# LED_Matrix.net
KiCad netlist of a schematic drawn in Altium Designer
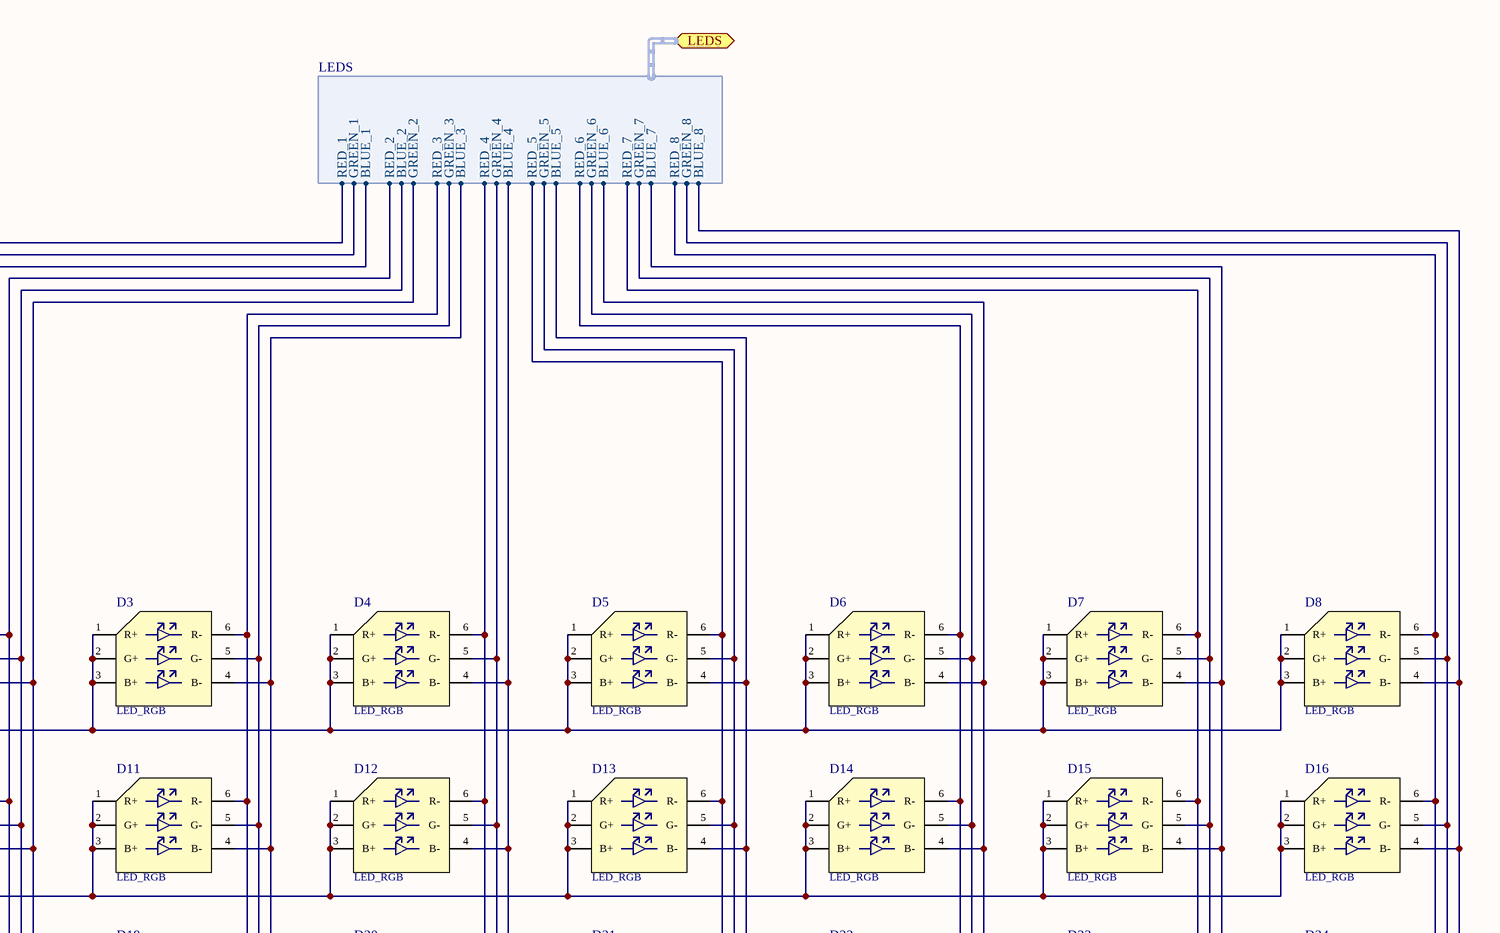
[diagram p0: LED Matrix.SchDoc, top right]
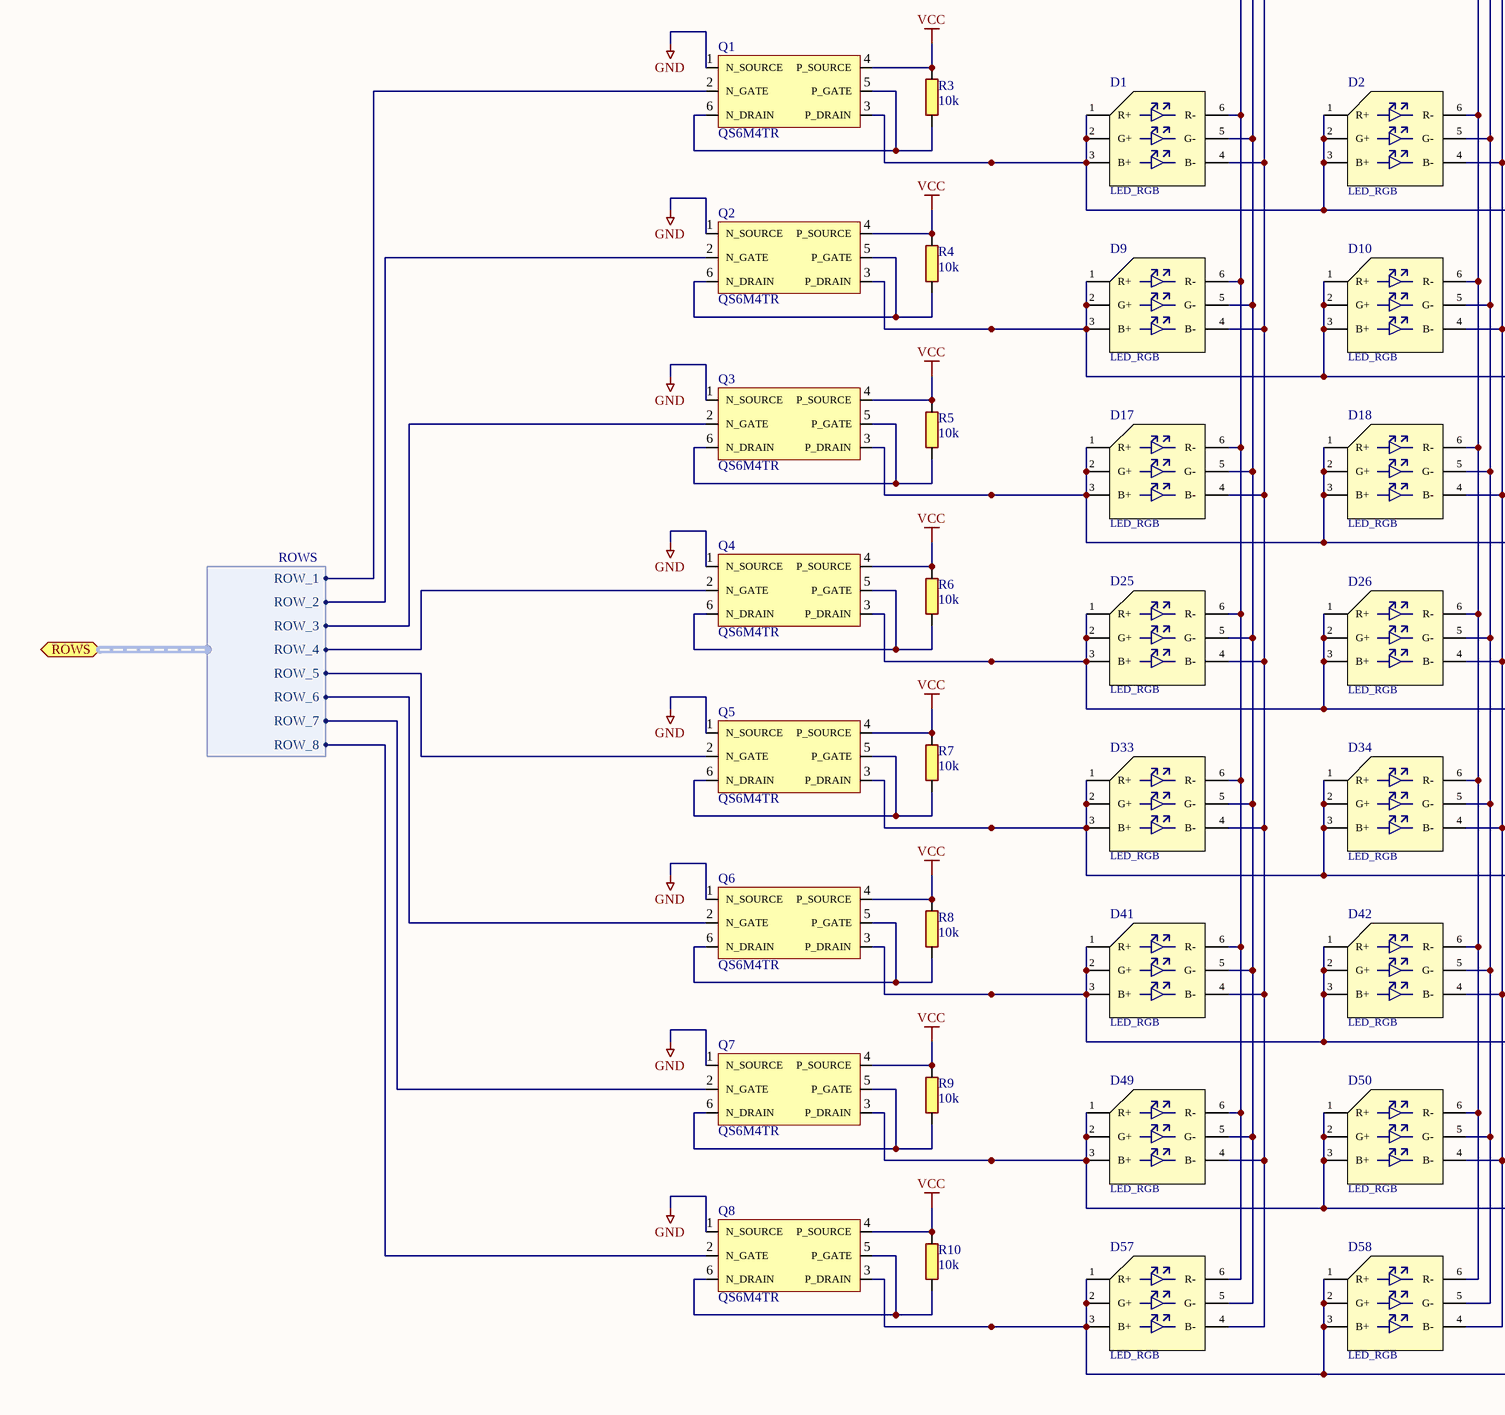
[diagram p1: LED Matrix.SchDoc, bottom left]
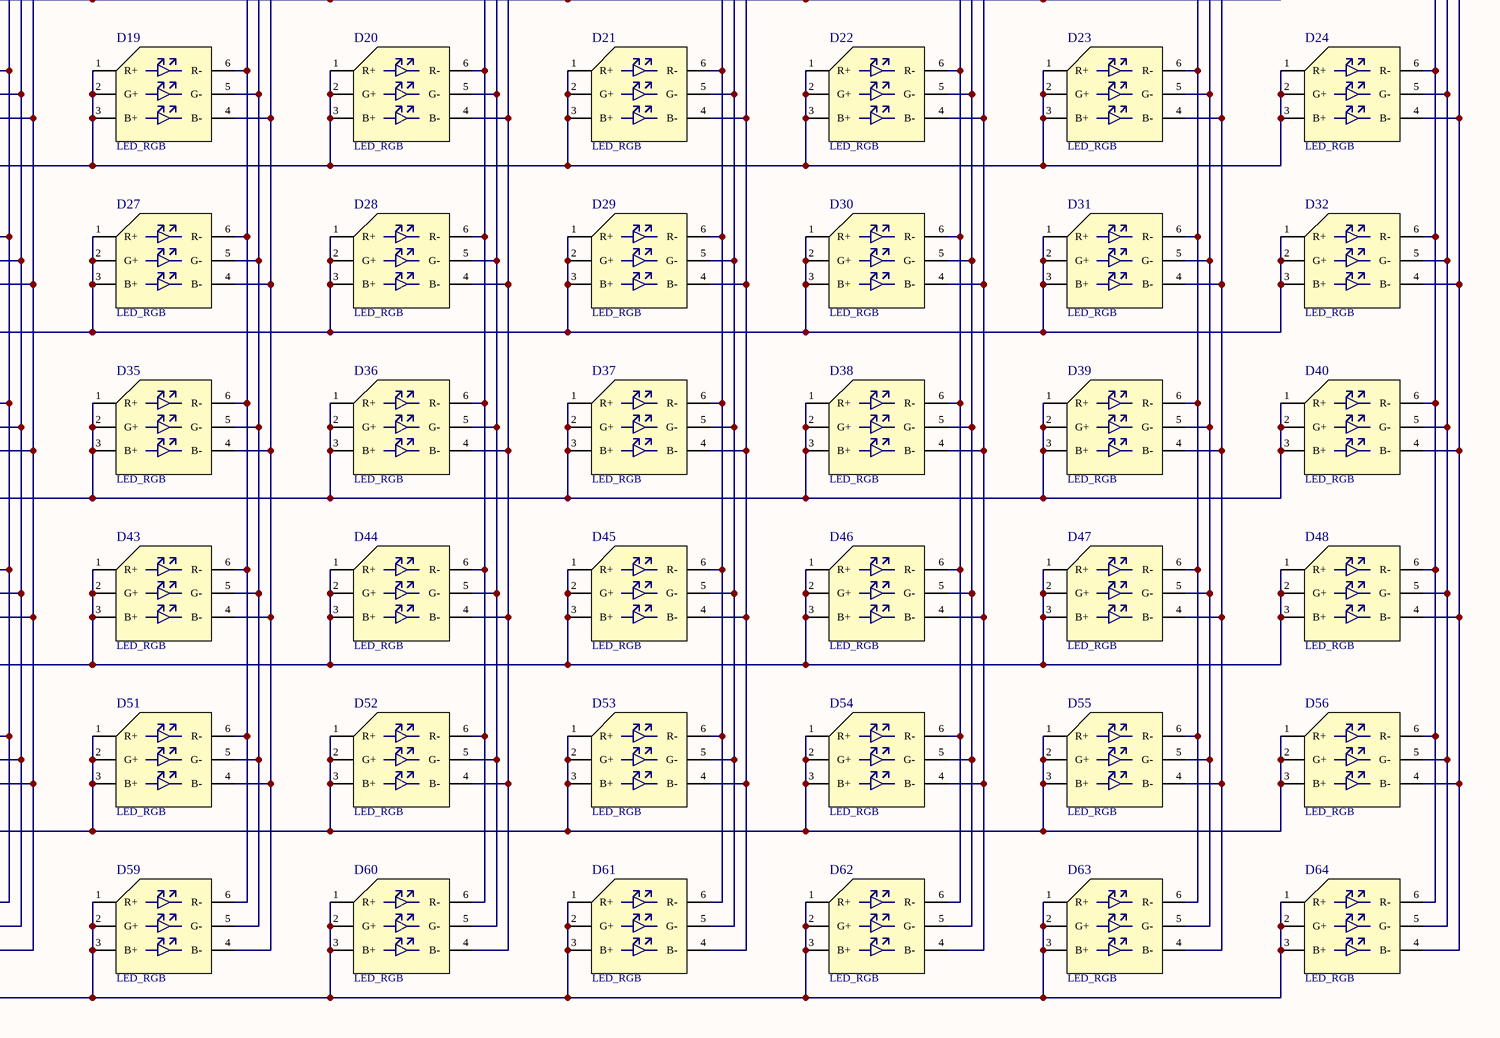
[diagram p2: LED Matrix.SchDoc, bottom right]

(export (version "E")
  (design (tool "Eeschema 10.0.6"))
  (components
    (comp (ref "D1")
      (value "LED_RGB")
      (footprint "LED5050_RGB_N")
      (description "LED RGB, independent colors")
      (libsource (lib "OVLib") (part "LED_RGB_IND_CHIP"))
    )
    (comp (ref "D2")
      (value "LED_RGB")
      (footprint "LED5050_RGB_N")
      (description "LED RGB, independent colors")
      (libsource (lib "OVLib") (part "LED_RGB_IND_CHIP"))
    )
    (comp (ref "D3")
      (value "LED_RGB")
      (footprint "LED5050_RGB_N")
      (description "LED RGB, independent colors")
      (libsource (lib "OVLib") (part "LED_RGB_IND_CHIP"))
    )
    (comp (ref "D4")
      (value "LED_RGB")
      (footprint "LED5050_RGB_N")
      (description "LED RGB, independent colors")
      (libsource (lib "OVLib") (part "LED_RGB_IND_CHIP"))
    )
    (comp (ref "D5")
      (value "LED_RGB")
      (footprint "LED5050_RGB_N")
      (description "LED RGB, independent colors")
      (libsource (lib "OVLib") (part "LED_RGB_IND_CHIP"))
    )
    (comp (ref "D6")
      (value "LED_RGB")
      (footprint "LED5050_RGB_N")
      (description "LED RGB, independent colors")
      (libsource (lib "OVLib") (part "LED_RGB_IND_CHIP"))
    )
    (comp (ref "D7")
      (value "LED_RGB")
      (footprint "LED5050_RGB_N")
      (description "LED RGB, independent colors")
      (libsource (lib "OVLib") (part "LED_RGB_IND_CHIP"))
    )
    (comp (ref "D8")
      (value "LED_RGB")
      (footprint "LED5050_RGB_N")
      (description "LED RGB, independent colors")
      (libsource (lib "OVLib") (part "LED_RGB_IND_CHIP"))
    )
    (comp (ref "D9")
      (value "LED_RGB")
      (footprint "LED5050_RGB_N")
      (description "LED RGB, independent colors")
      (libsource (lib "OVLib") (part "LED_RGB_IND_CHIP"))
    )
    (comp (ref "D10")
      (value "LED_RGB")
      (footprint "LED5050_RGB_N")
      (description "LED RGB, independent colors")
      (libsource (lib "OVLib") (part "LED_RGB_IND_CHIP"))
    )
    (comp (ref "D11")
      (value "LED_RGB")
      (footprint "LED5050_RGB_N")
      (description "LED RGB, independent colors")
      (libsource (lib "OVLib") (part "LED_RGB_IND_CHIP"))
    )
    (comp (ref "D12")
      (value "LED_RGB")
      (footprint "LED5050_RGB_N")
      (description "LED RGB, independent colors")
      (libsource (lib "OVLib") (part "LED_RGB_IND_CHIP"))
    )
    (comp (ref "D13")
      (value "LED_RGB")
      (footprint "LED5050_RGB_N")
      (description "LED RGB, independent colors")
      (libsource (lib "OVLib") (part "LED_RGB_IND_CHIP"))
    )
    (comp (ref "D14")
      (value "LED_RGB")
      (footprint "LED5050_RGB_N")
      (description "LED RGB, independent colors")
      (libsource (lib "OVLib") (part "LED_RGB_IND_CHIP"))
    )
    (comp (ref "D15")
      (value "LED_RGB")
      (footprint "LED5050_RGB_N")
      (description "LED RGB, independent colors")
      (libsource (lib "OVLib") (part "LED_RGB_IND_CHIP"))
    )
    (comp (ref "D16")
      (value "LED_RGB")
      (footprint "LED5050_RGB_N")
      (description "LED RGB, independent colors")
      (libsource (lib "OVLib") (part "LED_RGB_IND_CHIP"))
    )
    (comp (ref "D17")
      (value "LED_RGB")
      (footprint "LED5050_RGB_N")
      (description "LED RGB, independent colors")
      (libsource (lib "OVLib") (part "LED_RGB_IND_CHIP"))
    )
    (comp (ref "D18")
      (value "LED_RGB")
      (footprint "LED5050_RGB_N")
      (description "LED RGB, independent colors")
      (libsource (lib "OVLib") (part "LED_RGB_IND_CHIP"))
    )
    (comp (ref "D19")
      (value "LED_RGB")
      (footprint "LED5050_RGB_N")
      (description "LED RGB, independent colors")
      (libsource (lib "OVLib") (part "LED_RGB_IND_CHIP"))
    )
    (comp (ref "D20")
      (value "LED_RGB")
      (footprint "LED5050_RGB_N")
      (description "LED RGB, independent colors")
      (libsource (lib "OVLib") (part "LED_RGB_IND_CHIP"))
    )
    (comp (ref "D21")
      (value "LED_RGB")
      (footprint "LED5050_RGB_N")
      (description "LED RGB, independent colors")
      (libsource (lib "OVLib") (part "LED_RGB_IND_CHIP"))
    )
    (comp (ref "D22")
      (value "LED_RGB")
      (footprint "LED5050_RGB_N")
      (description "LED RGB, independent colors")
      (libsource (lib "OVLib") (part "LED_RGB_IND_CHIP"))
    )
    (comp (ref "D23")
      (value "LED_RGB")
      (footprint "LED5050_RGB_N")
      (description "LED RGB, independent colors")
      (libsource (lib "OVLib") (part "LED_RGB_IND_CHIP"))
    )
    (comp (ref "D24")
      (value "LED_RGB")
      (footprint "LED5050_RGB_N")
      (description "LED RGB, independent colors")
      (libsource (lib "OVLib") (part "LED_RGB_IND_CHIP"))
    )
    (comp (ref "D25")
      (value "LED_RGB")
      (footprint "LED5050_RGB_N")
      (description "LED RGB, independent colors")
      (libsource (lib "OVLib") (part "LED_RGB_IND_CHIP"))
    )
    (comp (ref "D26")
      (value "LED_RGB")
      (footprint "LED5050_RGB_N")
      (description "LED RGB, independent colors")
      (libsource (lib "OVLib") (part "LED_RGB_IND_CHIP"))
    )
    (comp (ref "D27")
      (value "LED_RGB")
      (footprint "LED5050_RGB_N")
      (description "LED RGB, independent colors")
      (libsource (lib "OVLib") (part "LED_RGB_IND_CHIP"))
    )
    (comp (ref "D28")
      (value "LED_RGB")
      (footprint "LED5050_RGB_N")
      (description "LED RGB, independent colors")
      (libsource (lib "OVLib") (part "LED_RGB_IND_CHIP"))
    )
    (comp (ref "D29")
      (value "LED_RGB")
      (footprint "LED5050_RGB_N")
      (description "LED RGB, independent colors")
      (libsource (lib "OVLib") (part "LED_RGB_IND_CHIP"))
    )
    (comp (ref "D30")
      (value "LED_RGB")
      (footprint "LED5050_RGB_N")
      (description "LED RGB, independent colors")
      (libsource (lib "OVLib") (part "LED_RGB_IND_CHIP"))
    )
    (comp (ref "D31")
      (value "LED_RGB")
      (footprint "LED5050_RGB_N")
      (description "LED RGB, independent colors")
      (libsource (lib "OVLib") (part "LED_RGB_IND_CHIP"))
    )
    (comp (ref "D32")
      (value "LED_RGB")
      (footprint "LED5050_RGB_N")
      (description "LED RGB, independent colors")
      (libsource (lib "OVLib") (part "LED_RGB_IND_CHIP"))
    )
    (comp (ref "D33")
      (value "LED_RGB")
      (footprint "LED5050_RGB_N")
      (description "LED RGB, independent colors")
      (libsource (lib "OVLib") (part "LED_RGB_IND_CHIP"))
    )
    (comp (ref "D34")
      (value "LED_RGB")
      (footprint "LED5050_RGB_N")
      (description "LED RGB, independent colors")
      (libsource (lib "OVLib") (part "LED_RGB_IND_CHIP"))
    )
    (comp (ref "D35")
      (value "LED_RGB")
      (footprint "LED5050_RGB_N")
      (description "LED RGB, independent colors")
      (libsource (lib "OVLib") (part "LED_RGB_IND_CHIP"))
    )
    (comp (ref "D36")
      (value "LED_RGB")
      (footprint "LED5050_RGB_N")
      (description "LED RGB, independent colors")
      (libsource (lib "OVLib") (part "LED_RGB_IND_CHIP"))
    )
    (comp (ref "D37")
      (value "LED_RGB")
      (footprint "LED5050_RGB_N")
      (description "LED RGB, independent colors")
      (libsource (lib "OVLib") (part "LED_RGB_IND_CHIP"))
    )
    (comp (ref "D38")
      (value "LED_RGB")
      (footprint "LED5050_RGB_N")
      (description "LED RGB, independent colors")
      (libsource (lib "OVLib") (part "LED_RGB_IND_CHIP"))
    )
    (comp (ref "D39")
      (value "LED_RGB")
      (footprint "LED5050_RGB_N")
      (description "LED RGB, independent colors")
      (libsource (lib "OVLib") (part "LED_RGB_IND_CHIP"))
    )
    (comp (ref "D40")
      (value "LED_RGB")
      (footprint "LED5050_RGB_N")
      (description "LED RGB, independent colors")
      (libsource (lib "OVLib") (part "LED_RGB_IND_CHIP"))
    )
    (comp (ref "D41")
      (value "LED_RGB")
      (footprint "LED5050_RGB_N")
      (description "LED RGB, independent colors")
      (libsource (lib "OVLib") (part "LED_RGB_IND_CHIP"))
    )
    (comp (ref "D42")
      (value "LED_RGB")
      (footprint "LED5050_RGB_N")
      (description "LED RGB, independent colors")
      (libsource (lib "OVLib") (part "LED_RGB_IND_CHIP"))
    )
    (comp (ref "D43")
      (value "LED_RGB")
      (footprint "LED5050_RGB_N")
      (description "LED RGB, independent colors")
      (libsource (lib "OVLib") (part "LED_RGB_IND_CHIP"))
    )
    (comp (ref "D44")
      (value "LED_RGB")
      (footprint "LED5050_RGB_N")
      (description "LED RGB, independent colors")
      (libsource (lib "OVLib") (part "LED_RGB_IND_CHIP"))
    )
    (comp (ref "D45")
      (value "LED_RGB")
      (footprint "LED5050_RGB_N")
      (description "LED RGB, independent colors")
      (libsource (lib "OVLib") (part "LED_RGB_IND_CHIP"))
    )
    (comp (ref "D46")
      (value "LED_RGB")
      (footprint "LED5050_RGB_N")
      (description "LED RGB, independent colors")
      (libsource (lib "OVLib") (part "LED_RGB_IND_CHIP"))
    )
    (comp (ref "D47")
      (value "LED_RGB")
      (footprint "LED5050_RGB_N")
      (description "LED RGB, independent colors")
      (libsource (lib "OVLib") (part "LED_RGB_IND_CHIP"))
    )
    (comp (ref "D48")
      (value "LED_RGB")
      (footprint "LED5050_RGB_N")
      (description "LED RGB, independent colors")
      (libsource (lib "OVLib") (part "LED_RGB_IND_CHIP"))
    )
    (comp (ref "D49")
      (value "LED_RGB")
      (footprint "LED5050_RGB_N")
      (description "LED RGB, independent colors")
      (libsource (lib "OVLib") (part "LED_RGB_IND_CHIP"))
    )
    (comp (ref "D50")
      (value "LED_RGB")
      (footprint "LED5050_RGB_N")
      (description "LED RGB, independent colors")
      (libsource (lib "OVLib") (part "LED_RGB_IND_CHIP"))
    )
    (comp (ref "D51")
      (value "LED_RGB")
      (footprint "LED5050_RGB_N")
      (description "LED RGB, independent colors")
      (libsource (lib "OVLib") (part "LED_RGB_IND_CHIP"))
    )
    (comp (ref "D52")
      (value "LED_RGB")
      (footprint "LED5050_RGB_N")
      (description "LED RGB, independent colors")
      (libsource (lib "OVLib") (part "LED_RGB_IND_CHIP"))
    )
    (comp (ref "D53")
      (value "LED_RGB")
      (footprint "LED5050_RGB_N")
      (description "LED RGB, independent colors")
      (libsource (lib "OVLib") (part "LED_RGB_IND_CHIP"))
    )
    (comp (ref "D54")
      (value "LED_RGB")
      (footprint "LED5050_RGB_N")
      (description "LED RGB, independent colors")
      (libsource (lib "OVLib") (part "LED_RGB_IND_CHIP"))
    )
    (comp (ref "D55")
      (value "LED_RGB")
      (footprint "LED5050_RGB_N")
      (description "LED RGB, independent colors")
      (libsource (lib "OVLib") (part "LED_RGB_IND_CHIP"))
    )
    (comp (ref "D56")
      (value "LED_RGB")
      (footprint "LED5050_RGB_N")
      (description "LED RGB, independent colors")
      (libsource (lib "OVLib") (part "LED_RGB_IND_CHIP"))
    )
    (comp (ref "D57")
      (value "LED_RGB")
      (footprint "LED5050_RGB_N")
      (description "LED RGB, independent colors")
      (libsource (lib "OVLib") (part "LED_RGB_IND_CHIP"))
    )
    (comp (ref "D58")
      (value "LED_RGB")
      (footprint "LED5050_RGB_N")
      (description "LED RGB, independent colors")
      (libsource (lib "OVLib") (part "LED_RGB_IND_CHIP"))
    )
    (comp (ref "D59")
      (value "LED_RGB")
      (footprint "LED5050_RGB_N")
      (description "LED RGB, independent colors")
      (libsource (lib "OVLib") (part "LED_RGB_IND_CHIP"))
    )
    (comp (ref "D60")
      (value "LED_RGB")
      (footprint "LED5050_RGB_N")
      (description "LED RGB, independent colors")
      (libsource (lib "OVLib") (part "LED_RGB_IND_CHIP"))
    )
    (comp (ref "D61")
      (value "LED_RGB")
      (footprint "LED5050_RGB_N")
      (description "LED RGB, independent colors")
      (libsource (lib "OVLib") (part "LED_RGB_IND_CHIP"))
    )
    (comp (ref "D62")
      (value "LED_RGB")
      (footprint "LED5050_RGB_N")
      (description "LED RGB, independent colors")
      (libsource (lib "OVLib") (part "LED_RGB_IND_CHIP"))
    )
    (comp (ref "D63")
      (value "LED_RGB")
      (footprint "LED5050_RGB_N")
      (description "LED RGB, independent colors")
      (libsource (lib "OVLib") (part "LED_RGB_IND_CHIP"))
    )
    (comp (ref "D64")
      (value "LED_RGB")
      (footprint "LED5050_RGB_N")
      (description "LED RGB, independent colors")
      (libsource (lib "OVLib") (part "LED_RGB_IND_CHIP"))
    )
    (comp (ref "Q1") (value "QS6M4TR") (libsource (lib "Schlib1") (part "QS6M4TR")))
    (comp (ref "Q2") (value "QS6M4TR") (libsource (lib "Schlib1") (part "QS6M4TR")))
    (comp (ref "Q3") (value "QS6M4TR") (libsource (lib "Schlib1") (part "QS6M4TR")))
    (comp (ref "Q4") (value "QS6M4TR") (libsource (lib "Schlib1") (part "QS6M4TR")))
    (comp (ref "Q5") (value "QS6M4TR") (libsource (lib "Schlib1") (part "QS6M4TR")))
    (comp (ref "Q6") (value "QS6M4TR") (libsource (lib "Schlib1") (part "QS6M4TR")))
    (comp (ref "Q7") (value "QS6M4TR") (libsource (lib "Schlib1") (part "QS6M4TR")))
    (comp (ref "Q8") (value "QS6M4TR") (libsource (lib "Schlib1") (part "QS6M4TR")))
    (comp (ref "R3")
      (value "10k")
      (footprint "RESC0603(1608)_N")
      (description "0.1W 1% Thick film resistor")
      (libsource (lib "OVLib") (part "Resistor2"))
    )
    (comp (ref "R4")
      (value "10k")
      (footprint "RESC0603(1608)_N")
      (description "0.1W 1% Thick film resistor")
      (libsource (lib "OVLib") (part "Resistor2"))
    )
    (comp (ref "R5")
      (value "10k")
      (footprint "RESC0603(1608)_N")
      (description "0.1W 1% Thick film resistor")
      (libsource (lib "OVLib") (part "Resistor2"))
    )
    (comp (ref "R6")
      (value "10k")
      (footprint "RESC0603(1608)_N")
      (description "0.1W 1% Thick film resistor")
      (libsource (lib "OVLib") (part "Resistor2"))
    )
    (comp (ref "R7")
      (value "10k")
      (footprint "RESC0603(1608)_N")
      (description "0.1W 1% Thick film resistor")
      (libsource (lib "OVLib") (part "Resistor2"))
    )
    (comp (ref "R8")
      (value "10k")
      (footprint "RESC0603(1608)_N")
      (description "0.1W 1% Thick film resistor")
      (libsource (lib "OVLib") (part "Resistor2"))
    )
    (comp (ref "R9")
      (value "10k")
      (footprint "RESC0603(1608)_N")
      (description "0.1W 1% Thick film resistor")
      (libsource (lib "OVLib") (part "Resistor2"))
    )
    (comp (ref "R10")
      (value "10k")
      (footprint "RESC0603(1608)_N")
      (description "0.1W 1% Thick film resistor")
      (libsource (lib "OVLib") (part "Resistor2"))
    )
  )
  (nets
    (net (code "3") (name "/BLUE_4") (class "Default")
      (node (ref "D12") (pin "4") (pinfunction "B-_4") (pintype "power_in"))
      (node (ref "D20") (pin "4") (pinfunction "B-_4") (pintype "power_in"))
      (node (ref "D28") (pin "4") (pinfunction "B-_4") (pintype "power_in"))
      (node (ref "D36") (pin "4") (pinfunction "B-_4") (pintype "power_in"))
      (node (ref "D4") (pin "4") (pinfunction "B-_4") (pintype "power_in"))
      (node (ref "D44") (pin "4") (pinfunction "B-_4") (pintype "power_in"))
      (node (ref "D52") (pin "4") (pinfunction "B-_4") (pintype "power_in"))
      (node (ref "D60") (pin "4") (pinfunction "B-_4") (pintype "power_in"))
    )
    (net (code "6") (name "GND") (class "Default")
      (node (ref "Q1") (pin "1") (pinfunction "N_SOURCE_1") (pintype "passive"))
      (node (ref "Q2") (pin "1") (pinfunction "N_SOURCE_1") (pintype "passive"))
      (node (ref "Q3") (pin "1") (pinfunction "N_SOURCE_1") (pintype "passive"))
      (node (ref "Q4") (pin "1") (pinfunction "N_SOURCE_1") (pintype "passive"))
      (node (ref "Q5") (pin "1") (pinfunction "N_SOURCE_1") (pintype "passive"))
      (node (ref "Q6") (pin "1") (pinfunction "N_SOURCE_1") (pintype "passive"))
      (node (ref "Q7") (pin "1") (pinfunction "N_SOURCE_1") (pintype "passive"))
      (node (ref "Q8") (pin "1") (pinfunction "N_SOURCE_1") (pintype "passive"))
    )
    (net (code "7") (name "Net-(D1-B+)") (class "Default")
      (node (ref "D1") (pin "1") (pinfunction "R+_1") (pintype "power_in"))
      (node (ref "D1") (pin "2") (pinfunction "G+_2") (pintype "power_in"))
      (node (ref "D1") (pin "3") (pinfunction "B+_3") (pintype "power_in"))
      (node (ref "D2") (pin "1") (pinfunction "R+_1") (pintype "power_in"))
      (node (ref "D2") (pin "2") (pinfunction "G+_2") (pintype "power_in"))
      (node (ref "D2") (pin "3") (pinfunction "B+_3") (pintype "power_in"))
      (node (ref "D3") (pin "1") (pinfunction "R+_1") (pintype "power_in"))
      (node (ref "D3") (pin "2") (pinfunction "G+_2") (pintype "power_in"))
      (node (ref "D3") (pin "3") (pinfunction "B+_3") (pintype "power_in"))
      (node (ref "D4") (pin "1") (pinfunction "R+_1") (pintype "power_in"))
      (node (ref "D4") (pin "2") (pinfunction "G+_2") (pintype "power_in"))
      (node (ref "D4") (pin "3") (pinfunction "B+_3") (pintype "power_in"))
      (node (ref "D5") (pin "1") (pinfunction "R+_1") (pintype "power_in"))
      (node (ref "D5") (pin "2") (pinfunction "G+_2") (pintype "power_in"))
      (node (ref "D5") (pin "3") (pinfunction "B+_3") (pintype "power_in"))
      (node (ref "D6") (pin "1") (pinfunction "R+_1") (pintype "power_in"))
      (node (ref "D6") (pin "2") (pinfunction "G+_2") (pintype "power_in"))
      (node (ref "D6") (pin "3") (pinfunction "B+_3") (pintype "power_in"))
      (node (ref "D7") (pin "1") (pinfunction "R+_1") (pintype "power_in"))
      (node (ref "D7") (pin "2") (pinfunction "G+_2") (pintype "power_in"))
      (node (ref "D7") (pin "3") (pinfunction "B+_3") (pintype "power_in"))
      (node (ref "D8") (pin "1") (pinfunction "R+_1") (pintype "power_in"))
      (node (ref "D8") (pin "2") (pinfunction "G+_2") (pintype "power_in"))
      (node (ref "D8") (pin "3") (pinfunction "B+_3") (pintype "power_in"))
      (node (ref "Q1") (pin "3") (pinfunction "P_DRAIN_3") (pintype "passive"))
    )
    (net (code "8") (name "Net-(D1-B-)") (class "Default")
      (node (ref "D1") (pin "4") (pinfunction "B-_4") (pintype "power_in"))
      (node (ref "D17") (pin "4") (pinfunction "B-_4") (pintype "power_in"))
      (node (ref "D25") (pin "4") (pinfunction "B-_4") (pintype "power_in"))
      (node (ref "D33") (pin "4") (pinfunction "B-_4") (pintype "power_in"))
      (node (ref "D41") (pin "4") (pinfunction "B-_4") (pintype "power_in"))
      (node (ref "D49") (pin "4") (pinfunction "B-_4") (pintype "power_in"))
      (node (ref "D57") (pin "4") (pinfunction "B-_4") (pintype "power_in"))
      (node (ref "D9") (pin "4") (pinfunction "B-_4") (pintype "power_in"))
    )
    (net (code "9") (name "Net-(D1-G-)") (class "Default")
      (node (ref "D1") (pin "5") (pinfunction "G-_5") (pintype "power_in"))
      (node (ref "D17") (pin "5") (pinfunction "G-_5") (pintype "power_in"))
      (node (ref "D25") (pin "5") (pinfunction "G-_5") (pintype "power_in"))
      (node (ref "D33") (pin "5") (pinfunction "G-_5") (pintype "power_in"))
      (node (ref "D41") (pin "5") (pinfunction "G-_5") (pintype "power_in"))
      (node (ref "D49") (pin "5") (pinfunction "G-_5") (pintype "power_in"))
      (node (ref "D57") (pin "5") (pinfunction "G-_5") (pintype "power_in"))
      (node (ref "D9") (pin "5") (pinfunction "G-_5") (pintype "power_in"))
    )
    (net (code "10") (name "Net-(D1-R-)") (class "Default")
      (node (ref "D1") (pin "6") (pinfunction "R-_6") (pintype "power_in"))
      (node (ref "D17") (pin "6") (pinfunction "R-_6") (pintype "power_in"))
      (node (ref "D25") (pin "6") (pinfunction "R-_6") (pintype "power_in"))
      (node (ref "D33") (pin "6") (pinfunction "R-_6") (pintype "power_in"))
      (node (ref "D41") (pin "6") (pinfunction "R-_6") (pintype "power_in"))
      (node (ref "D49") (pin "6") (pinfunction "R-_6") (pintype "power_in"))
      (node (ref "D57") (pin "6") (pinfunction "R-_6") (pintype "power_in"))
      (node (ref "D9") (pin "6") (pinfunction "R-_6") (pintype "power_in"))
    )
    (net (code "11") (name "Net-(D10-B+)") (class "Default")
      (node (ref "D10") (pin "1") (pinfunction "R+_1") (pintype "power_in"))
      (node (ref "D10") (pin "2") (pinfunction "G+_2") (pintype "power_in"))
      (node (ref "D10") (pin "3") (pinfunction "B+_3") (pintype "power_in"))
      (node (ref "D11") (pin "1") (pinfunction "R+_1") (pintype "power_in"))
      (node (ref "D11") (pin "2") (pinfunction "G+_2") (pintype "power_in"))
      (node (ref "D11") (pin "3") (pinfunction "B+_3") (pintype "power_in"))
      (node (ref "D12") (pin "1") (pinfunction "R+_1") (pintype "power_in"))
      (node (ref "D12") (pin "2") (pinfunction "G+_2") (pintype "power_in"))
      (node (ref "D12") (pin "3") (pinfunction "B+_3") (pintype "power_in"))
      (node (ref "D13") (pin "1") (pinfunction "R+_1") (pintype "power_in"))
      (node (ref "D13") (pin "2") (pinfunction "G+_2") (pintype "power_in"))
      (node (ref "D13") (pin "3") (pinfunction "B+_3") (pintype "power_in"))
      (node (ref "D14") (pin "1") (pinfunction "R+_1") (pintype "power_in"))
      (node (ref "D14") (pin "2") (pinfunction "G+_2") (pintype "power_in"))
      (node (ref "D14") (pin "3") (pinfunction "B+_3") (pintype "power_in"))
      (node (ref "D15") (pin "1") (pinfunction "R+_1") (pintype "power_in"))
      (node (ref "D15") (pin "2") (pinfunction "G+_2") (pintype "power_in"))
      (node (ref "D15") (pin "3") (pinfunction "B+_3") (pintype "power_in"))
      (node (ref "D16") (pin "1") (pinfunction "R+_1") (pintype "power_in"))
      (node (ref "D16") (pin "2") (pinfunction "G+_2") (pintype "power_in"))
      (node (ref "D16") (pin "3") (pinfunction "B+_3") (pintype "power_in"))
      (node (ref "D9") (pin "1") (pinfunction "R+_1") (pintype "power_in"))
      (node (ref "D9") (pin "2") (pinfunction "G+_2") (pintype "power_in"))
      (node (ref "D9") (pin "3") (pinfunction "B+_3") (pintype "power_in"))
      (node (ref "Q2") (pin "3") (pinfunction "P_DRAIN_3") (pintype "passive"))
    )
    (net (code "12") (name "Net-(D10-B-)") (class "Default")
      (node (ref "D10") (pin "4") (pinfunction "B-_4") (pintype "power_in"))
      (node (ref "D18") (pin "4") (pinfunction "B-_4") (pintype "power_in"))
      (node (ref "D2") (pin "4") (pinfunction "B-_4") (pintype "power_in"))
      (node (ref "D26") (pin "4") (pinfunction "B-_4") (pintype "power_in"))
      (node (ref "D34") (pin "4") (pinfunction "B-_4") (pintype "power_in"))
      (node (ref "D42") (pin "4") (pinfunction "B-_4") (pintype "power_in"))
      (node (ref "D50") (pin "4") (pinfunction "B-_4") (pintype "power_in"))
      (node (ref "D58") (pin "4") (pinfunction "B-_4") (pintype "power_in"))
    )
    (net (code "13") (name "Net-(D10-G-)") (class "Default")
      (node (ref "D10") (pin "5") (pinfunction "G-_5") (pintype "power_in"))
      (node (ref "D18") (pin "5") (pinfunction "G-_5") (pintype "power_in"))
      (node (ref "D2") (pin "5") (pinfunction "G-_5") (pintype "power_in"))
      (node (ref "D26") (pin "5") (pinfunction "G-_5") (pintype "power_in"))
      (node (ref "D34") (pin "5") (pinfunction "G-_5") (pintype "power_in"))
      (node (ref "D42") (pin "5") (pinfunction "G-_5") (pintype "power_in"))
      (node (ref "D50") (pin "5") (pinfunction "G-_5") (pintype "power_in"))
      (node (ref "D58") (pin "5") (pinfunction "G-_5") (pintype "power_in"))
    )
    (net (code "14") (name "Net-(D10-R-)") (class "Default")
      (node (ref "D10") (pin "6") (pinfunction "R-_6") (pintype "power_in"))
      (node (ref "D18") (pin "6") (pinfunction "R-_6") (pintype "power_in"))
      (node (ref "D2") (pin "6") (pinfunction "R-_6") (pintype "power_in"))
      (node (ref "D26") (pin "6") (pinfunction "R-_6") (pintype "power_in"))
      (node (ref "D34") (pin "6") (pinfunction "R-_6") (pintype "power_in"))
      (node (ref "D42") (pin "6") (pinfunction "R-_6") (pintype "power_in"))
      (node (ref "D50") (pin "6") (pinfunction "R-_6") (pintype "power_in"))
      (node (ref "D58") (pin "6") (pinfunction "R-_6") (pintype "power_in"))
    )
    (net (code "15") (name "Net-(D11-B-)") (class "Default")
      (node (ref "D11") (pin "4") (pinfunction "B-_4") (pintype "power_in"))
      (node (ref "D19") (pin "4") (pinfunction "B-_4") (pintype "power_in"))
      (node (ref "D27") (pin "4") (pinfunction "B-_4") (pintype "power_in"))
      (node (ref "D3") (pin "4") (pinfunction "B-_4") (pintype "power_in"))
      (node (ref "D35") (pin "4") (pinfunction "B-_4") (pintype "power_in"))
      (node (ref "D43") (pin "4") (pinfunction "B-_4") (pintype "power_in"))
      (node (ref "D51") (pin "4") (pinfunction "B-_4") (pintype "power_in"))
      (node (ref "D59") (pin "4") (pinfunction "B-_4") (pintype "power_in"))
    )
    (net (code "16") (name "Net-(D11-G-)") (class "Default")
      (node (ref "D11") (pin "5") (pinfunction "G-_5") (pintype "power_in"))
      (node (ref "D19") (pin "5") (pinfunction "G-_5") (pintype "power_in"))
      (node (ref "D27") (pin "5") (pinfunction "G-_5") (pintype "power_in"))
      (node (ref "D3") (pin "5") (pinfunction "G-_5") (pintype "power_in"))
      (node (ref "D35") (pin "5") (pinfunction "G-_5") (pintype "power_in"))
      (node (ref "D43") (pin "5") (pinfunction "G-_5") (pintype "power_in"))
      (node (ref "D51") (pin "5") (pinfunction "G-_5") (pintype "power_in"))
      (node (ref "D59") (pin "5") (pinfunction "G-_5") (pintype "power_in"))
    )
    (net (code "17") (name "Net-(D11-R-)") (class "Default")
      (node (ref "D11") (pin "6") (pinfunction "R-_6") (pintype "power_in"))
      (node (ref "D19") (pin "6") (pinfunction "R-_6") (pintype "power_in"))
      (node (ref "D27") (pin "6") (pinfunction "R-_6") (pintype "power_in"))
      (node (ref "D3") (pin "6") (pinfunction "R-_6") (pintype "power_in"))
      (node (ref "D35") (pin "6") (pinfunction "R-_6") (pintype "power_in"))
      (node (ref "D43") (pin "6") (pinfunction "R-_6") (pintype "power_in"))
      (node (ref "D51") (pin "6") (pinfunction "R-_6") (pintype "power_in"))
      (node (ref "D59") (pin "6") (pinfunction "R-_6") (pintype "power_in"))
    )
    (net (code "18") (name "Net-(D12-G-)") (class "Default")
      (node (ref "D12") (pin "5") (pinfunction "G-_5") (pintype "power_in"))
      (node (ref "D20") (pin "5") (pinfunction "G-_5") (pintype "power_in"))
      (node (ref "D28") (pin "5") (pinfunction "G-_5") (pintype "power_in"))
      (node (ref "D36") (pin "5") (pinfunction "G-_5") (pintype "power_in"))
      (node (ref "D4") (pin "5") (pinfunction "G-_5") (pintype "power_in"))
      (node (ref "D44") (pin "5") (pinfunction "G-_5") (pintype "power_in"))
      (node (ref "D52") (pin "5") (pinfunction "G-_5") (pintype "power_in"))
      (node (ref "D60") (pin "5") (pinfunction "G-_5") (pintype "power_in"))
    )
    (net (code "19") (name "Net-(D12-R-)") (class "Default")
      (node (ref "D12") (pin "6") (pinfunction "R-_6") (pintype "power_in"))
      (node (ref "D20") (pin "6") (pinfunction "R-_6") (pintype "power_in"))
      (node (ref "D28") (pin "6") (pinfunction "R-_6") (pintype "power_in"))
      (node (ref "D36") (pin "6") (pinfunction "R-_6") (pintype "power_in"))
      (node (ref "D4") (pin "6") (pinfunction "R-_6") (pintype "power_in"))
      (node (ref "D44") (pin "6") (pinfunction "R-_6") (pintype "power_in"))
      (node (ref "D52") (pin "6") (pinfunction "R-_6") (pintype "power_in"))
      (node (ref "D60") (pin "6") (pinfunction "R-_6") (pintype "power_in"))
    )
    (net (code "20") (name "Net-(D13-B-)") (class "Default")
      (node (ref "D13") (pin "4") (pinfunction "B-_4") (pintype "power_in"))
      (node (ref "D21") (pin "4") (pinfunction "B-_4") (pintype "power_in"))
      (node (ref "D29") (pin "4") (pinfunction "B-_4") (pintype "power_in"))
      (node (ref "D37") (pin "4") (pinfunction "B-_4") (pintype "power_in"))
      (node (ref "D45") (pin "4") (pinfunction "B-_4") (pintype "power_in"))
      (node (ref "D5") (pin "4") (pinfunction "B-_4") (pintype "power_in"))
      (node (ref "D53") (pin "4") (pinfunction "B-_4") (pintype "power_in"))
      (node (ref "D61") (pin "4") (pinfunction "B-_4") (pintype "power_in"))
    )
    (net (code "21") (name "Net-(D13-G-)") (class "Default")
      (node (ref "D13") (pin "5") (pinfunction "G-_5") (pintype "power_in"))
      (node (ref "D21") (pin "5") (pinfunction "G-_5") (pintype "power_in"))
      (node (ref "D29") (pin "5") (pinfunction "G-_5") (pintype "power_in"))
      (node (ref "D37") (pin "5") (pinfunction "G-_5") (pintype "power_in"))
      (node (ref "D45") (pin "5") (pinfunction "G-_5") (pintype "power_in"))
      (node (ref "D5") (pin "5") (pinfunction "G-_5") (pintype "power_in"))
      (node (ref "D53") (pin "5") (pinfunction "G-_5") (pintype "power_in"))
      (node (ref "D61") (pin "5") (pinfunction "G-_5") (pintype "power_in"))
    )
    (net (code "22") (name "Net-(D13-R-)") (class "Default")
      (node (ref "D13") (pin "6") (pinfunction "R-_6") (pintype "power_in"))
      (node (ref "D21") (pin "6") (pinfunction "R-_6") (pintype "power_in"))
      (node (ref "D29") (pin "6") (pinfunction "R-_6") (pintype "power_in"))
      (node (ref "D37") (pin "6") (pinfunction "R-_6") (pintype "power_in"))
      (node (ref "D45") (pin "6") (pinfunction "R-_6") (pintype "power_in"))
      (node (ref "D5") (pin "6") (pinfunction "R-_6") (pintype "power_in"))
      (node (ref "D53") (pin "6") (pinfunction "R-_6") (pintype "power_in"))
      (node (ref "D61") (pin "6") (pinfunction "R-_6") (pintype "power_in"))
    )
    (net (code "23") (name "Net-(D14-B-)") (class "Default")
      (node (ref "D14") (pin "4") (pinfunction "B-_4") (pintype "power_in"))
      (node (ref "D22") (pin "4") (pinfunction "B-_4") (pintype "power_in"))
      (node (ref "D30") (pin "4") (pinfunction "B-_4") (pintype "power_in"))
      (node (ref "D38") (pin "4") (pinfunction "B-_4") (pintype "power_in"))
      (node (ref "D46") (pin "4") (pinfunction "B-_4") (pintype "power_in"))
      (node (ref "D54") (pin "4") (pinfunction "B-_4") (pintype "power_in"))
      (node (ref "D6") (pin "4") (pinfunction "B-_4") (pintype "power_in"))
      (node (ref "D62") (pin "4") (pinfunction "B-_4") (pintype "power_in"))
    )
    (net (code "24") (name "Net-(D14-G-)") (class "Default")
      (node (ref "D14") (pin "5") (pinfunction "G-_5") (pintype "power_in"))
      (node (ref "D22") (pin "5") (pinfunction "G-_5") (pintype "power_in"))
      (node (ref "D30") (pin "5") (pinfunction "G-_5") (pintype "power_in"))
      (node (ref "D38") (pin "5") (pinfunction "G-_5") (pintype "power_in"))
      (node (ref "D46") (pin "5") (pinfunction "G-_5") (pintype "power_in"))
      (node (ref "D54") (pin "5") (pinfunction "G-_5") (pintype "power_in"))
      (node (ref "D6") (pin "5") (pinfunction "G-_5") (pintype "power_in"))
      (node (ref "D62") (pin "5") (pinfunction "G-_5") (pintype "power_in"))
    )
    (net (code "25") (name "Net-(D14-R-)") (class "Default")
      (node (ref "D14") (pin "6") (pinfunction "R-_6") (pintype "power_in"))
      (node (ref "D22") (pin "6") (pinfunction "R-_6") (pintype "power_in"))
      (node (ref "D30") (pin "6") (pinfunction "R-_6") (pintype "power_in"))
      (node (ref "D38") (pin "6") (pinfunction "R-_6") (pintype "power_in"))
      (node (ref "D46") (pin "6") (pinfunction "R-_6") (pintype "power_in"))
      (node (ref "D54") (pin "6") (pinfunction "R-_6") (pintype "power_in"))
      (node (ref "D6") (pin "6") (pinfunction "R-_6") (pintype "power_in"))
      (node (ref "D62") (pin "6") (pinfunction "R-_6") (pintype "power_in"))
    )
    (net (code "26") (name "Net-(D15-B-)") (class "Default")
      (node (ref "D15") (pin "4") (pinfunction "B-_4") (pintype "power_in"))
      (node (ref "D23") (pin "4") (pinfunction "B-_4") (pintype "power_in"))
      (node (ref "D31") (pin "4") (pinfunction "B-_4") (pintype "power_in"))
      (node (ref "D39") (pin "4") (pinfunction "B-_4") (pintype "power_in"))
      (node (ref "D47") (pin "4") (pinfunction "B-_4") (pintype "power_in"))
      (node (ref "D55") (pin "4") (pinfunction "B-_4") (pintype "power_in"))
      (node (ref "D63") (pin "4") (pinfunction "B-_4") (pintype "power_in"))
      (node (ref "D7") (pin "4") (pinfunction "B-_4") (pintype "power_in"))
    )
    (net (code "27") (name "Net-(D15-G-)") (class "Default")
      (node (ref "D15") (pin "5") (pinfunction "G-_5") (pintype "power_in"))
      (node (ref "D23") (pin "5") (pinfunction "G-_5") (pintype "power_in"))
      (node (ref "D31") (pin "5") (pinfunction "G-_5") (pintype "power_in"))
      (node (ref "D39") (pin "5") (pinfunction "G-_5") (pintype "power_in"))
      (node (ref "D47") (pin "5") (pinfunction "G-_5") (pintype "power_in"))
      (node (ref "D55") (pin "5") (pinfunction "G-_5") (pintype "power_in"))
      (node (ref "D63") (pin "5") (pinfunction "G-_5") (pintype "power_in"))
      (node (ref "D7") (pin "5") (pinfunction "G-_5") (pintype "power_in"))
    )
    (net (code "28") (name "Net-(D15-R-)") (class "Default")
      (node (ref "D15") (pin "6") (pinfunction "R-_6") (pintype "power_in"))
      (node (ref "D23") (pin "6") (pinfunction "R-_6") (pintype "power_in"))
      (node (ref "D31") (pin "6") (pinfunction "R-_6") (pintype "power_in"))
      (node (ref "D39") (pin "6") (pinfunction "R-_6") (pintype "power_in"))
      (node (ref "D47") (pin "6") (pinfunction "R-_6") (pintype "power_in"))
      (node (ref "D55") (pin "6") (pinfunction "R-_6") (pintype "power_in"))
      (node (ref "D63") (pin "6") (pinfunction "R-_6") (pintype "power_in"))
      (node (ref "D7") (pin "6") (pinfunction "R-_6") (pintype "power_in"))
    )
    (net (code "29") (name "Net-(D16-B-)") (class "Default")
      (node (ref "D16") (pin "4") (pinfunction "B-_4") (pintype "power_in"))
      (node (ref "D24") (pin "4") (pinfunction "B-_4") (pintype "power_in"))
      (node (ref "D32") (pin "4") (pinfunction "B-_4") (pintype "power_in"))
      (node (ref "D40") (pin "4") (pinfunction "B-_4") (pintype "power_in"))
      (node (ref "D48") (pin "4") (pinfunction "B-_4") (pintype "power_in"))
      (node (ref "D56") (pin "4") (pinfunction "B-_4") (pintype "power_in"))
      (node (ref "D64") (pin "4") (pinfunction "B-_4") (pintype "power_in"))
      (node (ref "D8") (pin "4") (pinfunction "B-_4") (pintype "power_in"))
    )
    (net (code "30") (name "Net-(D16-G-)") (class "Default")
      (node (ref "D16") (pin "5") (pinfunction "G-_5") (pintype "power_in"))
      (node (ref "D24") (pin "5") (pinfunction "G-_5") (pintype "power_in"))
      (node (ref "D32") (pin "5") (pinfunction "G-_5") (pintype "power_in"))
      (node (ref "D40") (pin "5") (pinfunction "G-_5") (pintype "power_in"))
      (node (ref "D48") (pin "5") (pinfunction "G-_5") (pintype "power_in"))
      (node (ref "D56") (pin "5") (pinfunction "G-_5") (pintype "power_in"))
      (node (ref "D64") (pin "5") (pinfunction "G-_5") (pintype "power_in"))
      (node (ref "D8") (pin "5") (pinfunction "G-_5") (pintype "power_in"))
    )
    (net (code "31") (name "Net-(D16-R-)") (class "Default")
      (node (ref "D16") (pin "6") (pinfunction "R-_6") (pintype "power_in"))
      (node (ref "D24") (pin "6") (pinfunction "R-_6") (pintype "power_in"))
      (node (ref "D32") (pin "6") (pinfunction "R-_6") (pintype "power_in"))
      (node (ref "D40") (pin "6") (pinfunction "R-_6") (pintype "power_in"))
      (node (ref "D48") (pin "6") (pinfunction "R-_6") (pintype "power_in"))
      (node (ref "D56") (pin "6") (pinfunction "R-_6") (pintype "power_in"))
      (node (ref "D64") (pin "6") (pinfunction "R-_6") (pintype "power_in"))
      (node (ref "D8") (pin "6") (pinfunction "R-_6") (pintype "power_in"))
    )
    (net (code "32") (name "Net-(D17-B+)") (class "Default")
      (node (ref "D17") (pin "1") (pinfunction "R+_1") (pintype "power_in"))
      (node (ref "D17") (pin "2") (pinfunction "G+_2") (pintype "power_in"))
      (node (ref "D17") (pin "3") (pinfunction "B+_3") (pintype "power_in"))
      (node (ref "D18") (pin "1") (pinfunction "R+_1") (pintype "power_in"))
      (node (ref "D18") (pin "2") (pinfunction "G+_2") (pintype "power_in"))
      (node (ref "D18") (pin "3") (pinfunction "B+_3") (pintype "power_in"))
      (node (ref "D19") (pin "1") (pinfunction "R+_1") (pintype "power_in"))
      (node (ref "D19") (pin "2") (pinfunction "G+_2") (pintype "power_in"))
      (node (ref "D19") (pin "3") (pinfunction "B+_3") (pintype "power_in"))
      (node (ref "D20") (pin "1") (pinfunction "R+_1") (pintype "power_in"))
      (node (ref "D20") (pin "2") (pinfunction "G+_2") (pintype "power_in"))
      (node (ref "D20") (pin "3") (pinfunction "B+_3") (pintype "power_in"))
      (node (ref "D21") (pin "1") (pinfunction "R+_1") (pintype "power_in"))
      (node (ref "D21") (pin "2") (pinfunction "G+_2") (pintype "power_in"))
      (node (ref "D21") (pin "3") (pinfunction "B+_3") (pintype "power_in"))
      (node (ref "D22") (pin "1") (pinfunction "R+_1") (pintype "power_in"))
      (node (ref "D22") (pin "2") (pinfunction "G+_2") (pintype "power_in"))
      (node (ref "D22") (pin "3") (pinfunction "B+_3") (pintype "power_in"))
      (node (ref "D23") (pin "1") (pinfunction "R+_1") (pintype "power_in"))
      (node (ref "D23") (pin "2") (pinfunction "G+_2") (pintype "power_in"))
      (node (ref "D23") (pin "3") (pinfunction "B+_3") (pintype "power_in"))
      (node (ref "D24") (pin "1") (pinfunction "R+_1") (pintype "power_in"))
      (node (ref "D24") (pin "2") (pinfunction "G+_2") (pintype "power_in"))
      (node (ref "D24") (pin "3") (pinfunction "B+_3") (pintype "power_in"))
      (node (ref "Q3") (pin "3") (pinfunction "P_DRAIN_3") (pintype "passive"))
    )
    (net (code "33") (name "Net-(D25-B+)") (class "Default")
      (node (ref "D25") (pin "1") (pinfunction "R+_1") (pintype "power_in"))
      (node (ref "D25") (pin "2") (pinfunction "G+_2") (pintype "power_in"))
      (node (ref "D25") (pin "3") (pinfunction "B+_3") (pintype "power_in"))
      (node (ref "D26") (pin "1") (pinfunction "R+_1") (pintype "power_in"))
      (node (ref "D26") (pin "2") (pinfunction "G+_2") (pintype "power_in"))
      (node (ref "D26") (pin "3") (pinfunction "B+_3") (pintype "power_in"))
      (node (ref "D27") (pin "1") (pinfunction "R+_1") (pintype "power_in"))
      (node (ref "D27") (pin "2") (pinfunction "G+_2") (pintype "power_in"))
      (node (ref "D27") (pin "3") (pinfunction "B+_3") (pintype "power_in"))
      (node (ref "D28") (pin "1") (pinfunction "R+_1") (pintype "power_in"))
      (node (ref "D28") (pin "2") (pinfunction "G+_2") (pintype "power_in"))
      (node (ref "D28") (pin "3") (pinfunction "B+_3") (pintype "power_in"))
      (node (ref "D29") (pin "1") (pinfunction "R+_1") (pintype "power_in"))
      (node (ref "D29") (pin "2") (pinfunction "G+_2") (pintype "power_in"))
      (node (ref "D29") (pin "3") (pinfunction "B+_3") (pintype "power_in"))
      (node (ref "D30") (pin "1") (pinfunction "R+_1") (pintype "power_in"))
      (node (ref "D30") (pin "2") (pinfunction "G+_2") (pintype "power_in"))
      (node (ref "D30") (pin "3") (pinfunction "B+_3") (pintype "power_in"))
      (node (ref "D31") (pin "1") (pinfunction "R+_1") (pintype "power_in"))
      (node (ref "D31") (pin "2") (pinfunction "G+_2") (pintype "power_in"))
      (node (ref "D31") (pin "3") (pinfunction "B+_3") (pintype "power_in"))
      (node (ref "D32") (pin "1") (pinfunction "R+_1") (pintype "power_in"))
      (node (ref "D32") (pin "2") (pinfunction "G+_2") (pintype "power_in"))
      (node (ref "D32") (pin "3") (pinfunction "B+_3") (pintype "power_in"))
      (node (ref "Q4") (pin "3") (pinfunction "P_DRAIN_3") (pintype "passive"))
    )
    (net (code "34") (name "Net-(D33-B+)") (class "Default")
      (node (ref "D33") (pin "1") (pinfunction "R+_1") (pintype "power_in"))
      (node (ref "D33") (pin "2") (pinfunction "G+_2") (pintype "power_in"))
      (node (ref "D33") (pin "3") (pinfunction "B+_3") (pintype "power_in"))
      (node (ref "D34") (pin "1") (pinfunction "R+_1") (pintype "power_in"))
      (node (ref "D34") (pin "2") (pinfunction "G+_2") (pintype "power_in"))
      (node (ref "D34") (pin "3") (pinfunction "B+_3") (pintype "power_in"))
      (node (ref "D35") (pin "1") (pinfunction "R+_1") (pintype "power_in"))
      (node (ref "D35") (pin "2") (pinfunction "G+_2") (pintype "power_in"))
      (node (ref "D35") (pin "3") (pinfunction "B+_3") (pintype "power_in"))
      (node (ref "D36") (pin "1") (pinfunction "R+_1") (pintype "power_in"))
      (node (ref "D36") (pin "2") (pinfunction "G+_2") (pintype "power_in"))
      (node (ref "D36") (pin "3") (pinfunction "B+_3") (pintype "power_in"))
      (node (ref "D37") (pin "1") (pinfunction "R+_1") (pintype "power_in"))
      (node (ref "D37") (pin "2") (pinfunction "G+_2") (pintype "power_in"))
      (node (ref "D37") (pin "3") (pinfunction "B+_3") (pintype "power_in"))
      (node (ref "D38") (pin "1") (pinfunction "R+_1") (pintype "power_in"))
      (node (ref "D38") (pin "2") (pinfunction "G+_2") (pintype "power_in"))
      (node (ref "D38") (pin "3") (pinfunction "B+_3") (pintype "power_in"))
      (node (ref "D39") (pin "1") (pinfunction "R+_1") (pintype "power_in"))
      (node (ref "D39") (pin "2") (pinfunction "G+_2") (pintype "power_in"))
      (node (ref "D39") (pin "3") (pinfunction "B+_3") (pintype "power_in"))
      (node (ref "D40") (pin "1") (pinfunction "R+_1") (pintype "power_in"))
      (node (ref "D40") (pin "2") (pinfunction "G+_2") (pintype "power_in"))
      (node (ref "D40") (pin "3") (pinfunction "B+_3") (pintype "power_in"))
      (node (ref "Q5") (pin "3") (pinfunction "P_DRAIN_3") (pintype "passive"))
    )
    (net (code "35") (name "Net-(D41-B+)") (class "Default")
      (node (ref "D41") (pin "1") (pinfunction "R+_1") (pintype "power_in"))
      (node (ref "D41") (pin "2") (pinfunction "G+_2") (pintype "power_in"))
      (node (ref "D41") (pin "3") (pinfunction "B+_3") (pintype "power_in"))
      (node (ref "D42") (pin "1") (pinfunction "R+_1") (pintype "power_in"))
      (node (ref "D42") (pin "2") (pinfunction "G+_2") (pintype "power_in"))
      (node (ref "D42") (pin "3") (pinfunction "B+_3") (pintype "power_in"))
      (node (ref "D43") (pin "1") (pinfunction "R+_1") (pintype "power_in"))
      (node (ref "D43") (pin "2") (pinfunction "G+_2") (pintype "power_in"))
      (node (ref "D43") (pin "3") (pinfunction "B+_3") (pintype "power_in"))
      (node (ref "D44") (pin "1") (pinfunction "R+_1") (pintype "power_in"))
      (node (ref "D44") (pin "2") (pinfunction "G+_2") (pintype "power_in"))
      (node (ref "D44") (pin "3") (pinfunction "B+_3") (pintype "power_in"))
      (node (ref "D45") (pin "1") (pinfunction "R+_1") (pintype "power_in"))
      (node (ref "D45") (pin "2") (pinfunction "G+_2") (pintype "power_in"))
      (node (ref "D45") (pin "3") (pinfunction "B+_3") (pintype "power_in"))
      (node (ref "D46") (pin "1") (pinfunction "R+_1") (pintype "power_in"))
      (node (ref "D46") (pin "2") (pinfunction "G+_2") (pintype "power_in"))
      (node (ref "D46") (pin "3") (pinfunction "B+_3") (pintype "power_in"))
      (node (ref "D47") (pin "1") (pinfunction "R+_1") (pintype "power_in"))
      (node (ref "D47") (pin "2") (pinfunction "G+_2") (pintype "power_in"))
      (node (ref "D47") (pin "3") (pinfunction "B+_3") (pintype "power_in"))
      (node (ref "D48") (pin "1") (pinfunction "R+_1") (pintype "power_in"))
      (node (ref "D48") (pin "2") (pinfunction "G+_2") (pintype "power_in"))
      (node (ref "D48") (pin "3") (pinfunction "B+_3") (pintype "power_in"))
      (node (ref "Q6") (pin "3") (pinfunction "P_DRAIN_3") (pintype "passive"))
    )
    (net (code "36") (name "Net-(D49-B+)") (class "Default")
      (node (ref "D49") (pin "1") (pinfunction "R+_1") (pintype "power_in"))
      (node (ref "D49") (pin "2") (pinfunction "G+_2") (pintype "power_in"))
      (node (ref "D49") (pin "3") (pinfunction "B+_3") (pintype "power_in"))
      (node (ref "D50") (pin "1") (pinfunction "R+_1") (pintype "power_in"))
      (node (ref "D50") (pin "2") (pinfunction "G+_2") (pintype "power_in"))
      (node (ref "D50") (pin "3") (pinfunction "B+_3") (pintype "power_in"))
      (node (ref "D51") (pin "1") (pinfunction "R+_1") (pintype "power_in"))
      (node (ref "D51") (pin "2") (pinfunction "G+_2") (pintype "power_in"))
      (node (ref "D51") (pin "3") (pinfunction "B+_3") (pintype "power_in"))
      (node (ref "D52") (pin "1") (pinfunction "R+_1") (pintype "power_in"))
      (node (ref "D52") (pin "2") (pinfunction "G+_2") (pintype "power_in"))
      (node (ref "D52") (pin "3") (pinfunction "B+_3") (pintype "power_in"))
      (node (ref "D53") (pin "1") (pinfunction "R+_1") (pintype "power_in"))
      (node (ref "D53") (pin "2") (pinfunction "G+_2") (pintype "power_in"))
      (node (ref "D53") (pin "3") (pinfunction "B+_3") (pintype "power_in"))
      (node (ref "D54") (pin "1") (pinfunction "R+_1") (pintype "power_in"))
      (node (ref "D54") (pin "2") (pinfunction "G+_2") (pintype "power_in"))
      (node (ref "D54") (pin "3") (pinfunction "B+_3") (pintype "power_in"))
      (node (ref "D55") (pin "1") (pinfunction "R+_1") (pintype "power_in"))
      (node (ref "D55") (pin "2") (pinfunction "G+_2") (pintype "power_in"))
      (node (ref "D55") (pin "3") (pinfunction "B+_3") (pintype "power_in"))
      (node (ref "D56") (pin "1") (pinfunction "R+_1") (pintype "power_in"))
      (node (ref "D56") (pin "2") (pinfunction "G+_2") (pintype "power_in"))
      (node (ref "D56") (pin "3") (pinfunction "B+_3") (pintype "power_in"))
      (node (ref "Q7") (pin "3") (pinfunction "P_DRAIN_3") (pintype "passive"))
    )
    (net (code "37") (name "Net-(D57-B+)") (class "Default")
      (node (ref "D57") (pin "1") (pinfunction "R+_1") (pintype "power_in"))
      (node (ref "D57") (pin "2") (pinfunction "G+_2") (pintype "power_in"))
      (node (ref "D57") (pin "3") (pinfunction "B+_3") (pintype "power_in"))
      (node (ref "D58") (pin "1") (pinfunction "R+_1") (pintype "power_in"))
      (node (ref "D58") (pin "2") (pinfunction "G+_2") (pintype "power_in"))
      (node (ref "D58") (pin "3") (pinfunction "B+_3") (pintype "power_in"))
      (node (ref "D59") (pin "1") (pinfunction "R+_1") (pintype "power_in"))
      (node (ref "D59") (pin "2") (pinfunction "G+_2") (pintype "power_in"))
      (node (ref "D59") (pin "3") (pinfunction "B+_3") (pintype "power_in"))
      (node (ref "D60") (pin "1") (pinfunction "R+_1") (pintype "power_in"))
      (node (ref "D60") (pin "2") (pinfunction "G+_2") (pintype "power_in"))
      (node (ref "D60") (pin "3") (pinfunction "B+_3") (pintype "power_in"))
      (node (ref "D61") (pin "1") (pinfunction "R+_1") (pintype "power_in"))
      (node (ref "D61") (pin "2") (pinfunction "G+_2") (pintype "power_in"))
      (node (ref "D61") (pin "3") (pinfunction "B+_3") (pintype "power_in"))
      (node (ref "D62") (pin "1") (pinfunction "R+_1") (pintype "power_in"))
      (node (ref "D62") (pin "2") (pinfunction "G+_2") (pintype "power_in"))
      (node (ref "D62") (pin "3") (pinfunction "B+_3") (pintype "power_in"))
      (node (ref "D63") (pin "1") (pinfunction "R+_1") (pintype "power_in"))
      (node (ref "D63") (pin "2") (pinfunction "G+_2") (pintype "power_in"))
      (node (ref "D63") (pin "3") (pinfunction "B+_3") (pintype "power_in"))
      (node (ref "D64") (pin "1") (pinfunction "R+_1") (pintype "power_in"))
      (node (ref "D64") (pin "2") (pinfunction "G+_2") (pintype "power_in"))
      (node (ref "D64") (pin "3") (pinfunction "B+_3") (pintype "power_in"))
      (node (ref "Q8") (pin "3") (pinfunction "P_DRAIN_3") (pintype "passive"))
    )
    (net (code "38") (name "Net-(Q1-N_DRAIN)") (class "Default")
      (node (ref "Q1") (pin "5") (pinfunction "P_GATE_5") (pintype "passive"))
      (node (ref "Q1") (pin "6") (pinfunction "N_DRAIN_6") (pintype "passive"))
      (node (ref "R3") (pin "1") (pinfunction "1_1") (pintype "passive"))
    )
    (net (code "39") (name "Net-(Q2-N_DRAIN)") (class "Default")
      (node (ref "Q2") (pin "5") (pinfunction "P_GATE_5") (pintype "passive"))
      (node (ref "Q2") (pin "6") (pinfunction "N_DRAIN_6") (pintype "passive"))
      (node (ref "R4") (pin "1") (pinfunction "1_1") (pintype "passive"))
    )
    (net (code "40") (name "Net-(Q3-N_DRAIN)") (class "Default")
      (node (ref "Q3") (pin "5") (pinfunction "P_GATE_5") (pintype "passive"))
      (node (ref "Q3") (pin "6") (pinfunction "N_DRAIN_6") (pintype "passive"))
      (node (ref "R5") (pin "1") (pinfunction "1_1") (pintype "passive"))
    )
    (net (code "41") (name "Net-(Q4-N_DRAIN)") (class "Default")
      (node (ref "Q4") (pin "5") (pinfunction "P_GATE_5") (pintype "passive"))
      (node (ref "Q4") (pin "6") (pinfunction "N_DRAIN_6") (pintype "passive"))
      (node (ref "R6") (pin "1") (pinfunction "1_1") (pintype "passive"))
    )
    (net (code "42") (name "Net-(Q5-N_DRAIN)") (class "Default")
      (node (ref "Q5") (pin "5") (pinfunction "P_GATE_5") (pintype "passive"))
      (node (ref "Q5") (pin "6") (pinfunction "N_DRAIN_6") (pintype "passive"))
      (node (ref "R7") (pin "1") (pinfunction "1_1") (pintype "passive"))
    )
    (net (code "43") (name "Net-(Q6-N_DRAIN)") (class "Default")
      (node (ref "Q6") (pin "5") (pinfunction "P_GATE_5") (pintype "passive"))
      (node (ref "Q6") (pin "6") (pinfunction "N_DRAIN_6") (pintype "passive"))
      (node (ref "R8") (pin "1") (pinfunction "1_1") (pintype "passive"))
    )
    (net (code "44") (name "Net-(Q7-N_DRAIN)") (class "Default")
      (node (ref "Q7") (pin "5") (pinfunction "P_GATE_5") (pintype "passive"))
      (node (ref "Q7") (pin "6") (pinfunction "N_DRAIN_6") (pintype "passive"))
      (node (ref "R9") (pin "1") (pinfunction "1_1") (pintype "passive"))
    )
    (net (code "45") (name "Net-(Q8-N_DRAIN)") (class "Default")
      (node (ref "Q8") (pin "5") (pinfunction "P_GATE_5") (pintype "passive"))
      (node (ref "Q8") (pin "6") (pinfunction "N_DRAIN_6") (pintype "passive"))
      (node (ref "R10") (pin "1") (pinfunction "1_1") (pintype "passive"))
    )
    (net (code "46") (name "VCC") (class "Default")
      (node (ref "Q1") (pin "4") (pinfunction "P_SOURCE_4") (pintype "passive"))
      (node (ref "Q2") (pin "4") (pinfunction "P_SOURCE_4") (pintype "passive"))
      (node (ref "Q3") (pin "4") (pinfunction "P_SOURCE_4") (pintype "passive"))
      (node (ref "Q4") (pin "4") (pinfunction "P_SOURCE_4") (pintype "passive"))
      (node (ref "Q5") (pin "4") (pinfunction "P_SOURCE_4") (pintype "passive"))
      (node (ref "Q6") (pin "4") (pinfunction "P_SOURCE_4") (pintype "passive"))
      (node (ref "Q7") (pin "4") (pinfunction "P_SOURCE_4") (pintype "passive"))
      (node (ref "Q8") (pin "4") (pinfunction "P_SOURCE_4") (pintype "passive"))
      (node (ref "R10") (pin "2") (pinfunction "2_2") (pintype "passive"))
      (node (ref "R3") (pin "2") (pinfunction "2_2") (pintype "passive"))
      (node (ref "R4") (pin "2") (pinfunction "2_2") (pintype "passive"))
      (node (ref "R5") (pin "2") (pinfunction "2_2") (pintype "passive"))
      (node (ref "R6") (pin "2") (pinfunction "2_2") (pintype "passive"))
      (node (ref "R7") (pin "2") (pinfunction "2_2") (pintype "passive"))
      (node (ref "R8") (pin "2") (pinfunction "2_2") (pintype "passive"))
      (node (ref "R9") (pin "2") (pinfunction "2_2") (pintype "passive"))
    )
    (net (code "47") (name "unconnected-(Q1-N_GATE-Pad2)") (class "Default")
      (node (ref "Q1") (pin "2") (pinfunction "N_GATE_2") (pintype "passive"))
    )
    (net (code "48") (name "unconnected-(Q2-N_GATE-Pad2)") (class "Default")
      (node (ref "Q2") (pin "2") (pinfunction "N_GATE_2") (pintype "passive"))
    )
    (net (code "49") (name "unconnected-(Q3-N_GATE-Pad2)") (class "Default")
      (node (ref "Q3") (pin "2") (pinfunction "N_GATE_2") (pintype "passive"))
    )
    (net (code "50") (name "unconnected-(Q4-N_GATE-Pad2)") (class "Default")
      (node (ref "Q4") (pin "2") (pinfunction "N_GATE_2") (pintype "passive"))
    )
    (net (code "51") (name "unconnected-(Q5-N_GATE-Pad2)") (class "Default")
      (node (ref "Q5") (pin "2") (pinfunction "N_GATE_2") (pintype "passive"))
    )
    (net (code "52") (name "unconnected-(Q6-N_GATE-Pad2)") (class "Default")
      (node (ref "Q6") (pin "2") (pinfunction "N_GATE_2") (pintype "passive"))
    )
    (net (code "53") (name "unconnected-(Q7-N_GATE-Pad2)") (class "Default")
      (node (ref "Q7") (pin "2") (pinfunction "N_GATE_2") (pintype "passive"))
    )
    (net (code "54") (name "unconnected-(Q8-N_GATE-Pad2)") (class "Default")
      (node (ref "Q8") (pin "2") (pinfunction "N_GATE_2") (pintype "passive"))
    )
  )
)
